# localization-daughter-board.net
KiCad netlist of a schematic drawn in EAGLE
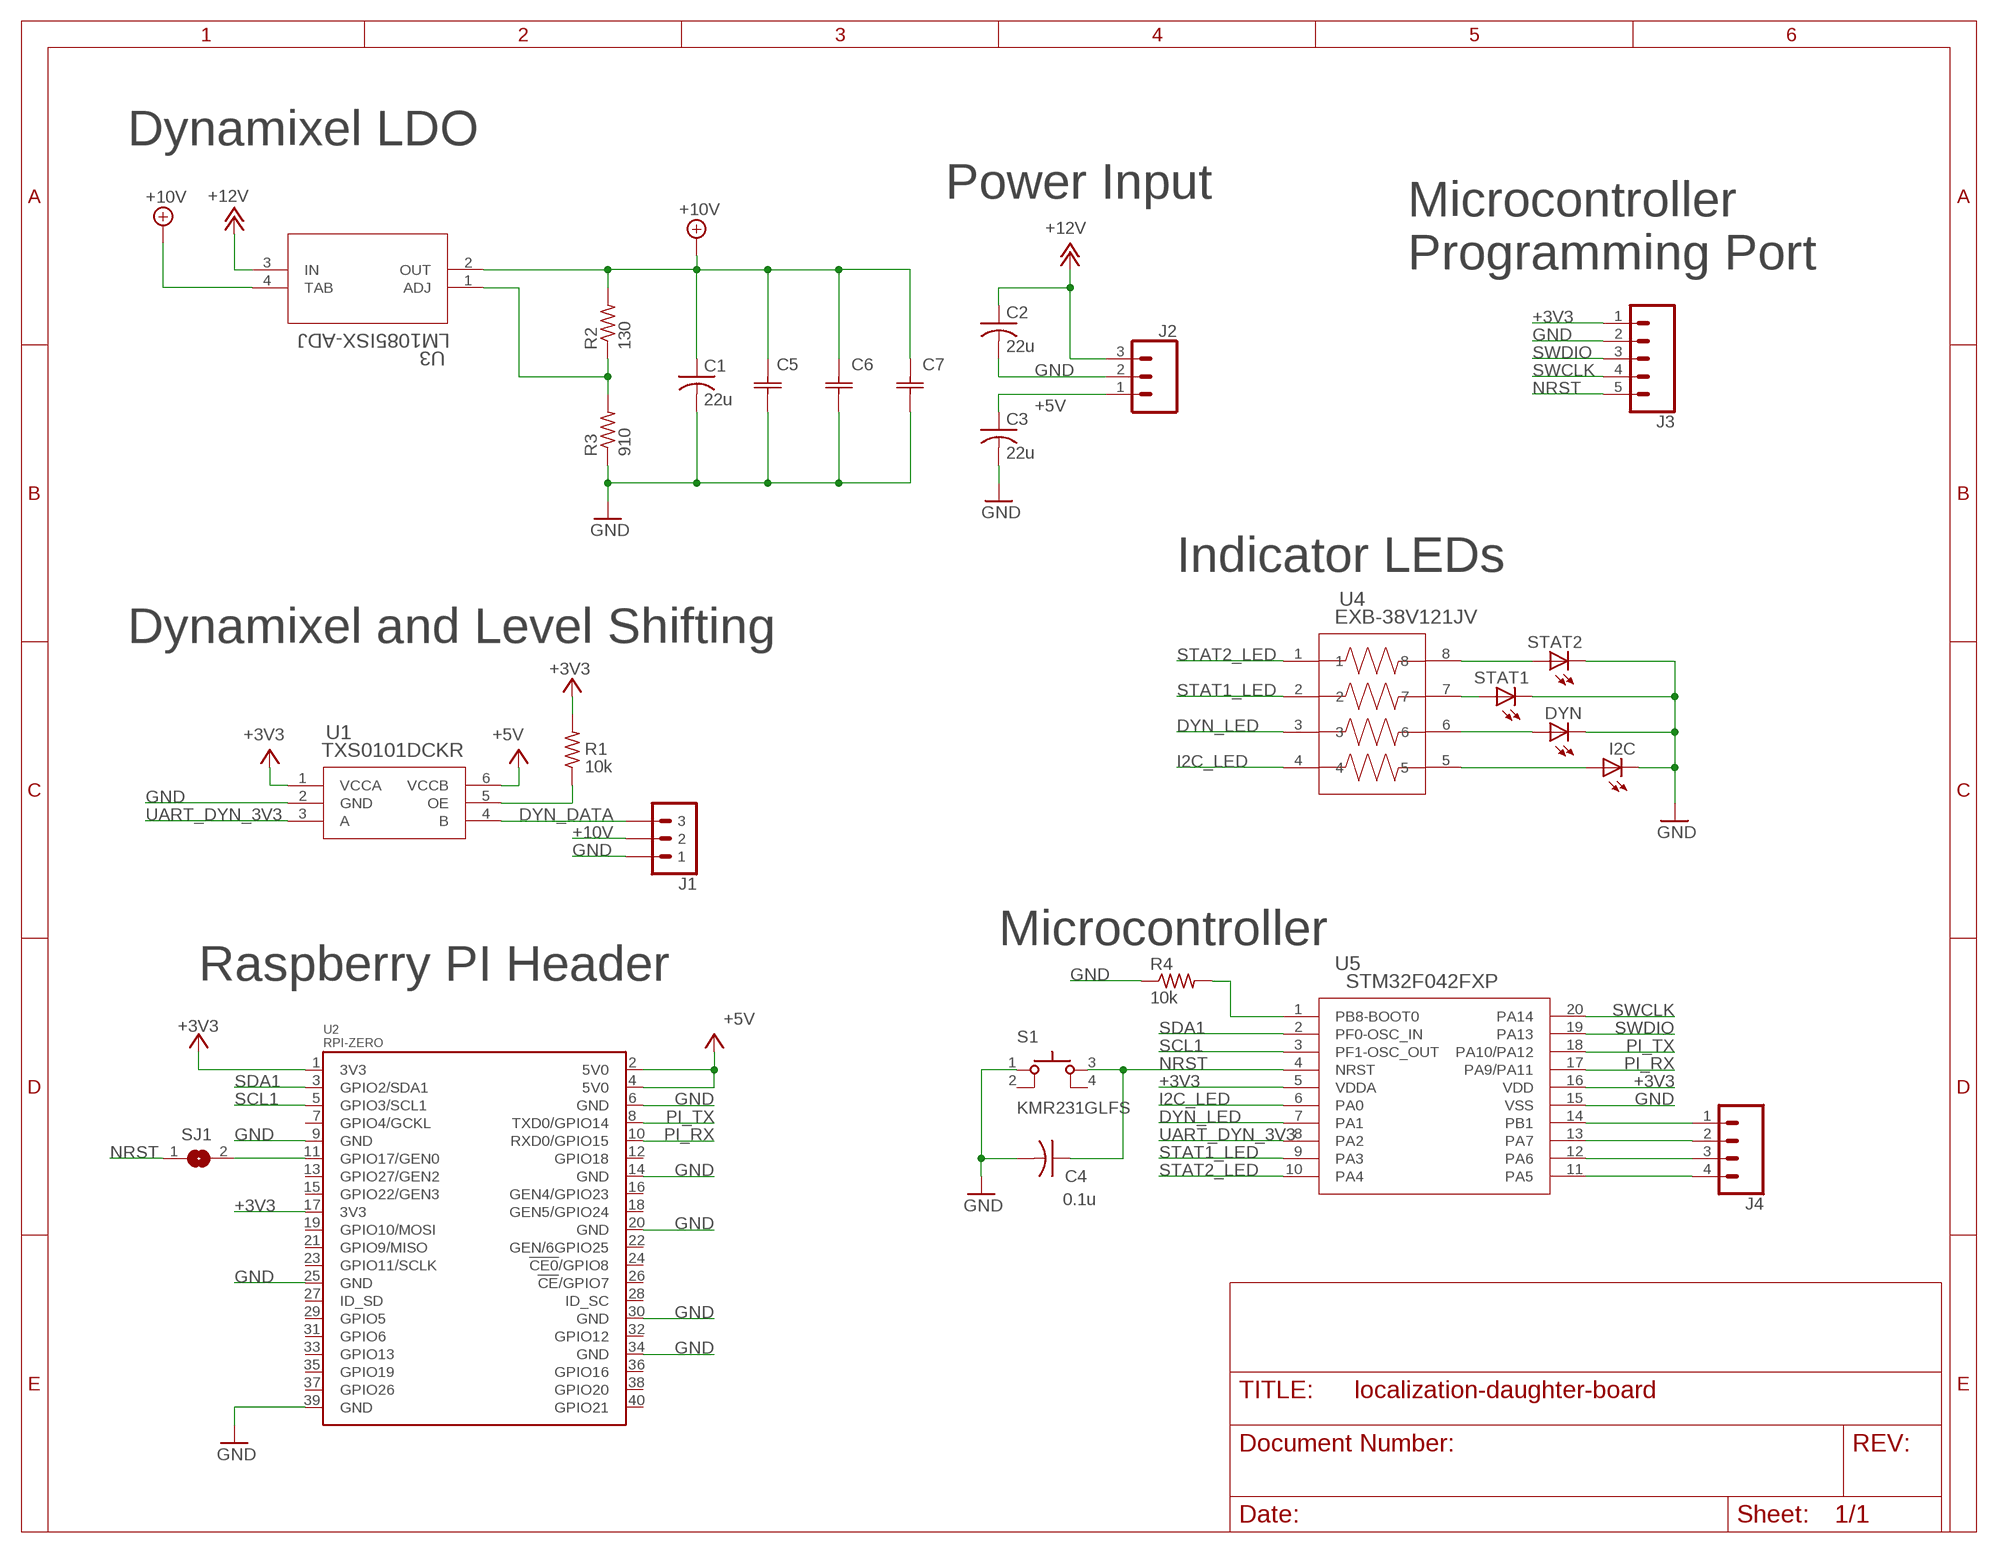
[diagram p0: schematic, sheet 1]

(export (version "E")
  (design (tool "Eeschema 10.0.6"))
  (components
    (comp (ref "C1")
      (value "22u")
      (footprint "eagle-import:C1206")
      (libsource (lib "eagle-import") (part "C-USC1206"))
    )
    (comp (ref "C2")
      (value "22u")
      (footprint "eagle-import:C0805")
      (libsource (lib "eagle-import") (part "C-USC0805"))
    )
    (comp (ref "C3")
      (value "22u")
      (footprint "eagle-import:C0805")
      (libsource (lib "eagle-import") (part "C-USC0805"))
    )
    (comp (ref "C4")
      (value "0.1u")
      (footprint "eagle-import:C0805")
      (libsource (lib "eagle-import") (part "C-USC0805"))
    )
    (comp (ref "C5")
      (value "F931C107MCC")
      (footprint "eagle-import:F93-C")
      (libsource (lib "eagle-import") (part "F931C107MCC"))
    )
    (comp (ref "C6")
      (value "F931C107MCC")
      (footprint "eagle-import:F93-C")
      (libsource (lib "eagle-import") (part "F931C107MCC"))
    )
    (comp (ref "C7")
      (value "F931C107MCC")
      (footprint "eagle-import:F93-C")
      (libsource (lib "eagle-import") (part "F931C107MCC"))
    )
    (comp (ref "DYN")
      (value "LEDSML0603")
      (footprint "eagle-import:SML0603")
      (libsource (lib "eagle-import") (part "LEDSML0603"))
    )
    (comp (ref "I2C")
      (value "LEDSML0603")
      (footprint "eagle-import:SML0603")
      (libsource (lib "eagle-import") (part "LEDSML0603"))
    )
    (comp (ref "J1")
      (value "MOLEX-22-03-5035")
      (footprint "eagle-import:MOLEX-22-05-7035")
      (libsource (lib "eagle-import") (part "MOLEX-22-03-5035"))
    )
    (comp (ref "J2")
      (value "CONN_03JST-PTH")
      (footprint "eagle-import:JST-3-PTH")
      (libsource (lib "eagle-import") (part "CONN_03JST-PTH"))
    )
    (comp (ref "J3")
      (value "CONN_05JST-VERT")
      (footprint "eagle-import:JST-5-PTH-VERT")
      (libsource (lib "eagle-import") (part "CONN_05JST-VERT"))
    )
    (comp (ref "J4")
      (value "CONN_041X04_NO_SILK")
      (footprint "eagle-import:1X04_NO_SILK")
      (libsource (lib "eagle-import") (part "CONN_041X04_NO_SILK"))
    )
    (comp (ref "R1")
      (value "10k")
      (footprint "eagle-import:R0805")
      (libsource (lib "eagle-import") (part "R-US_R0805"))
    )
    (comp (ref "R2")
      (value "130")
      (footprint "eagle-import:R0805")
      (libsource (lib "eagle-import") (part "R-US_R0805"))
    )
    (comp (ref "R3")
      (value "910")
      (footprint "eagle-import:R0805")
      (libsource (lib "eagle-import") (part "R-US_R0805"))
    )
    (comp (ref "R4")
      (value "10k")
      (footprint "eagle-import:R0805")
      (libsource (lib "eagle-import") (part "R-US_R0805"))
    )
    (comp (ref "S1")
      (value "KMR231GLFS")
      (footprint "eagle-import:KMR231GLFS")
      (libsource (lib "eagle-import") (part "KMR231GLFS"))
    )
    (comp (ref "SJ1") (value "SJ") (footprint "eagle-import:SJ") (libsource (lib "eagle-import") (part "SJ")))
    (comp (ref "STAT1")
      (value "LEDSML0603")
      (footprint "eagle-import:SML0603")
      (libsource (lib "eagle-import") (part "LEDSML0603"))
    )
    (comp (ref "STAT2")
      (value "LEDSML0603")
      (footprint "eagle-import:SML0603")
      (libsource (lib "eagle-import") (part "LEDSML0603"))
    )
    (comp (ref "U1")
      (value "TXS0101DCKR")
      (footprint "eagle-import:DCK6")
      (libsource (lib "eagle-import") (part "TXS0101DCKR"))
    )
    (comp (ref "U2")
      (value "RPI-ZERO")
      (footprint "eagle-import:RASPBERRYPI_BASTELSTUBE_V13_RASPI_BOARD_B+_FULL")
      (libsource (lib "eagle-import") (part "RPI-ZERO"))
    )
    (comp (ref "U3")
      (value "LM1085ISX-ADJ")
      (footprint "eagle-import:TS3B")
      (fields (field (name "MANUFACTURER_PART_NUMBER") "lm1085isxadj"))
      (libsource (lib "eagle-import") (part "LM1085ISX-ADJ"))
    )
    (comp (ref "U4")
      (value "EXB-38V121JV")
      (footprint "eagle-import:C_ARRAY_EXB38V")
      (fields (field (name "MANUFACTURER_PART_NUMBER") "EXB38V121JV"))
      (libsource (lib "eagle-import") (part "EXB-38V121JV"))
    )
    (comp (ref "U5")
      (value "STM32F042FXP")
      (footprint "eagle-import:TSSOP20")
      (fields (field (name "MANUFACTURER_PART_NUMBER") "STM32F042FxP"))
      (libsource (lib "eagle-import") (part "STM32F042FXP"))
    )
  )
  (nets
    (net (code "1") (name "+3V3") (class "Default")
      (node (ref "J3") (pin "1") (pinfunction "1_1") (pintype "passive"))
      (node (ref "R1") (pin "2") (pinfunction "2_2") (pintype "passive"))
      (node (ref "U1") (pin "1") (pinfunction "VCCA_1") (pintype "power_in"))
      (node (ref "U2") (pin "1") (pinfunction "3V3_1") (pintype "power_in"))
      (node (ref "U2") (pin "17") (pinfunction "3V3_17") (pintype "power_in"))
      (node (ref "U5") (pin "16") (pinfunction "VDD_16") (pintype "power_in"))
      (node (ref "U5") (pin "5") (pinfunction "VDDA_5") (pintype "power_in"))
    )
    (net (code "2") (name "+5V") (class "Default")
      (node (ref "C3") (pin "1") (pinfunction "1_1") (pintype "passive"))
      (node (ref "J2") (pin "1") (pinfunction "1_1") (pintype "passive"))
      (node (ref "U1") (pin "6") (pinfunction "VCCB_6") (pintype "power_in"))
      (node (ref "U2") (pin "2") (pinfunction "5V0_2") (pintype "power_in"))
      (node (ref "U2") (pin "4") (pinfunction "5V0_4") (pintype "power_in"))
    )
    (net (code "3") (name "+10V") (class "Default")
      (node (ref "C1") (pin "1") (pinfunction "1_1") (pintype "passive"))
      (node (ref "C5") (pin "1") (pinfunction "1_1") (pintype "passive"))
      (node (ref "C6") (pin "1") (pinfunction "1_1") (pintype "passive"))
      (node (ref "C7") (pin "1") (pinfunction "1_1") (pintype "passive"))
      (node (ref "J1") (pin "P$2") (pinfunction "2_P$2") (pintype "bidirectional"))
      (node (ref "R2") (pin "2") (pinfunction "2_2") (pintype "passive"))
      (node (ref "U3") (pin "2") (pinfunction "OUT_2") (pintype "power_in"))
      (node (ref "U3") (pin "4") (pinfunction "TAB_4") (pintype "power_in"))
    )
    (net (code "4") (name "+12V") (class "Default")
      (node (ref "C2") (pin "1") (pinfunction "1_1") (pintype "passive"))
      (node (ref "J2") (pin "3") (pinfunction "3_3") (pintype "passive"))
      (node (ref "U3") (pin "3") (pinfunction "IN_3") (pintype "power_in"))
    )
    (net (code "5") (name "/DYN_DATA") (class "Default")
      (node (ref "J1") (pin "P$3") (pinfunction "3_P$3") (pintype "bidirectional"))
      (node (ref "U1") (pin "4") (pinfunction "B_4") (pintype "bidirectional"))
    )
    (net (code "6") (name "/DYN_LED") (class "Default")
      (node (ref "U4") (pin "3") (pinfunction "3_3") (pintype "passive"))
      (node (ref "U5") (pin "7") (pinfunction "PA1_7") (pintype "bidirectional"))
    )
    (net (code "7") (name "/I2C_LED") (class "Default")
      (node (ref "U4") (pin "4") (pinfunction "4_4") (pintype "passive"))
      (node (ref "U5") (pin "6") (pinfunction "PA0_6") (pintype "bidirectional"))
    )
    (net (code "8") (name "/NRST") (class "Default")
      (node (ref "C4") (pin "1") (pinfunction "1_1") (pintype "passive"))
      (node (ref "J3") (pin "5") (pinfunction "5_5") (pintype "passive"))
      (node (ref "S1") (pin "3") (pinfunction "3_3") (pintype "bidirectional"))
      (node (ref "SJ1") (pin "1") (pinfunction "1_1") (pintype "passive"))
      (node (ref "U5") (pin "4") (pinfunction "NRST_4") (pintype "bidirectional"))
    )
    (net (code "9") (name "/PI_RX") (class "Default")
      (node (ref "U2") (pin "10") (pinfunction "RXD0/GPIO15_10") (pintype "bidirectional"))
      (node (ref "U5") (pin "17") (pinfunction "PA9/PA11_17") (pintype "bidirectional"))
    )
    (net (code "10") (name "/PI_TX") (class "Default")
      (node (ref "U2") (pin "8") (pinfunction "TXD0/GPIO14_8") (pintype "bidirectional"))
      (node (ref "U5") (pin "18") (pinfunction "PA10/PA12_18") (pintype "bidirectional"))
    )
    (net (code "11") (name "/SCL1") (class "Default")
      (node (ref "U2") (pin "5") (pinfunction "GPIO3/SCL1_5") (pintype "bidirectional"))
      (node (ref "U5") (pin "3") (pinfunction "PF1-OSC_OUT_3") (pintype "bidirectional"))
    )
    (net (code "12") (name "/SDA1") (class "Default")
      (node (ref "U2") (pin "3") (pinfunction "GPIO2/SDA1_3") (pintype "bidirectional"))
      (node (ref "U5") (pin "2") (pinfunction "PF0-OSC_IN_2") (pintype "bidirectional"))
    )
    (net (code "13") (name "/STAT1_LED") (class "Default")
      (node (ref "U4") (pin "2") (pinfunction "2_2") (pintype "passive"))
      (node (ref "U5") (pin "9") (pinfunction "PA3_9") (pintype "bidirectional"))
    )
    (net (code "14") (name "/STAT2_LED") (class "Default")
      (node (ref "U4") (pin "1") (pinfunction "1_1") (pintype "passive"))
      (node (ref "U5") (pin "10") (pinfunction "PA4_10") (pintype "bidirectional"))
    )
    (net (code "15") (name "/SWCLK") (class "Default")
      (node (ref "J3") (pin "4") (pinfunction "4_4") (pintype "passive"))
      (node (ref "U5") (pin "20") (pinfunction "PA14_20") (pintype "bidirectional"))
    )
    (net (code "16") (name "/SWDIO") (class "Default")
      (node (ref "J3") (pin "3") (pinfunction "3_3") (pintype "passive"))
      (node (ref "U5") (pin "19") (pinfunction "PA13_19") (pintype "bidirectional"))
    )
    (net (code "17") (name "/UART_DYN_3V3") (class "Default")
      (node (ref "U1") (pin "3") (pinfunction "A_3") (pintype "bidirectional"))
      (node (ref "U5") (pin "8") (pinfunction "PA2_8") (pintype "bidirectional"))
    )
    (net (code "18") (name "GND") (class "Default")
      (node (ref "C1") (pin "2") (pinfunction "2_2") (pintype "passive"))
      (node (ref "C2") (pin "2") (pinfunction "2_2") (pintype "passive"))
      (node (ref "C3") (pin "2") (pinfunction "2_2") (pintype "passive"))
      (node (ref "C4") (pin "2") (pinfunction "2_2") (pintype "passive"))
      (node (ref "C5") (pin "2") (pinfunction "2_2") (pintype "passive"))
      (node (ref "C6") (pin "2") (pinfunction "2_2") (pintype "passive"))
      (node (ref "C7") (pin "2") (pinfunction "2_2") (pintype "passive"))
      (node (ref "DYN") (pin "C") (pinfunction "C_C") (pintype "passive"))
      (node (ref "I2C") (pin "C") (pinfunction "C_C") (pintype "passive"))
      (node (ref "J1") (pin "P$1") (pinfunction "1_P$1") (pintype "bidirectional"))
      (node (ref "J2") (pin "2") (pinfunction "2_2") (pintype "passive"))
      (node (ref "J3") (pin "2") (pinfunction "2_2") (pintype "passive"))
      (node (ref "R3") (pin "1") (pinfunction "1_1") (pintype "passive"))
      (node (ref "R4") (pin "1") (pinfunction "1_1") (pintype "passive"))
      (node (ref "S1") (pin "1") (pinfunction "1_1") (pintype "bidirectional"))
      (node (ref "STAT1") (pin "C") (pinfunction "C_C") (pintype "passive"))
      (node (ref "STAT2") (pin "C") (pinfunction "C_C") (pintype "passive"))
      (node (ref "U1") (pin "2") (pinfunction "GND_2") (pintype "power_in"))
      (node (ref "U2") (pin "14") (pinfunction "GND_14") (pintype "power_in"))
      (node (ref "U2") (pin "20") (pinfunction "GND_20") (pintype "power_in"))
      (node (ref "U2") (pin "25") (pinfunction "GND_25") (pintype "power_in"))
      (node (ref "U2") (pin "30") (pinfunction "GND_30") (pintype "power_in"))
      (node (ref "U2") (pin "34") (pinfunction "GND_34") (pintype "power_in"))
      (node (ref "U2") (pin "39") (pinfunction "GND_39") (pintype "power_in"))
      (node (ref "U2") (pin "6") (pinfunction "GND_6") (pintype "power_in"))
      (node (ref "U2") (pin "9") (pinfunction "GND_9") (pintype "power_in"))
      (node (ref "U5") (pin "15") (pinfunction "VSS_15") (pintype "power_in"))
    )
    (net (code "19") (name "Net-(DYN-PadA)") (class "Default")
      (node (ref "DYN") (pin "A") (pinfunction "A_A") (pintype "passive"))
      (node (ref "U4") (pin "6") (pinfunction "6_6") (pintype "passive"))
    )
    (net (code "20") (name "Net-(I2C-PadA)") (class "Default")
      (node (ref "I2C") (pin "A") (pinfunction "A_A") (pintype "passive"))
      (node (ref "U4") (pin "5") (pinfunction "5_5") (pintype "passive"))
    )
    (net (code "21") (name "Net-(STAT1-PadA)") (class "Default")
      (node (ref "STAT1") (pin "A") (pinfunction "A_A") (pintype "passive"))
      (node (ref "U4") (pin "7") (pinfunction "7_7") (pintype "passive"))
    )
    (net (code "22") (name "Net-(STAT2-PadA)") (class "Default")
      (node (ref "STAT2") (pin "A") (pinfunction "A_A") (pintype "passive"))
      (node (ref "U4") (pin "8") (pinfunction "8_8") (pintype "passive"))
    )
    (net (code "23") (name "Net-(U1-OE)") (class "Default")
      (node (ref "R1") (pin "1") (pinfunction "1_1") (pintype "passive"))
      (node (ref "U1") (pin "5") (pinfunction "OE_5") (pintype "output"))
    )
    (net (code "24") (name "Net-(U2-GPIO17{slash}GEN0)") (class "Default")
      (node (ref "SJ1") (pin "2") (pinfunction "2_2") (pintype "passive"))
      (node (ref "U2") (pin "11") (pinfunction "GPIO17/GEN0_11") (pintype "bidirectional"))
    )
    (net (code "25") (name "Net-(U3-ADJ)") (class "Default")
      (node (ref "R2") (pin "1") (pinfunction "1_1") (pintype "passive"))
      (node (ref "R3") (pin "2") (pinfunction "2_2") (pintype "passive"))
      (node (ref "U3") (pin "1") (pinfunction "ADJ_1") (pintype "input"))
    )
    (net (code "26") (name "Net-(U5-PA5)") (class "Default")
      (node (ref "J4") (pin "4") (pinfunction "4_4") (pintype "passive"))
      (node (ref "U5") (pin "11") (pinfunction "PA5_11") (pintype "bidirectional"))
    )
    (net (code "27") (name "Net-(U5-PA6)") (class "Default")
      (node (ref "J4") (pin "3") (pinfunction "3_3") (pintype "passive"))
      (node (ref "U5") (pin "12") (pinfunction "PA6_12") (pintype "bidirectional"))
    )
    (net (code "28") (name "Net-(U5-PA7)") (class "Default")
      (node (ref "J4") (pin "2") (pinfunction "2_2") (pintype "passive"))
      (node (ref "U5") (pin "13") (pinfunction "PA7_13") (pintype "bidirectional"))
    )
    (net (code "29") (name "Net-(U5-PB1)") (class "Default")
      (node (ref "J4") (pin "1") (pinfunction "1_1") (pintype "passive"))
      (node (ref "U5") (pin "14") (pinfunction "PB1_14") (pintype "bidirectional"))
    )
    (net (code "30") (name "Net-(U5-PB8-BOOT0)") (class "Default")
      (node (ref "R4") (pin "2") (pinfunction "2_2") (pintype "passive"))
      (node (ref "U5") (pin "1") (pinfunction "PB8-BOOT0_1") (pintype "bidirectional"))
    )
    (net (code "31") (name "unconnected-(S1-Pad2)") (class "Default")
      (node (ref "S1") (pin "2") (pinfunction "2_2") (pintype "bidirectional"))
    )
    (net (code "32") (name "unconnected-(S1-Pad4)") (class "Default")
      (node (ref "S1") (pin "4") (pinfunction "4_4") (pintype "bidirectional"))
    )
    (net (code "33") (name "unconnected-(U2-GEN4{slash}GPIO23-Pad16)") (class "Default")
      (node (ref "U2") (pin "16") (pinfunction "GEN4/GPIO23_16") (pintype "bidirectional"))
    )
    (net (code "34") (name "unconnected-(U2-GEN5{slash}GPIO24-Pad18)") (class "Default")
      (node (ref "U2") (pin "18") (pinfunction "GEN5/GPIO24_18") (pintype "bidirectional"))
    )
    (net (code "35") (name "unconnected-(U2-GEN{slash}6GPIO25-Pad22)") (class "Default")
      (node (ref "U2") (pin "22") (pinfunction "GEN/6GPIO25_22") (pintype "bidirectional"))
    )
    (net (code "36") (name "unconnected-(U2-GPIO4{slash}GCKL-Pad7)") (class "Default")
      (node (ref "U2") (pin "7") (pinfunction "GPIO4/GCKL_7") (pintype "bidirectional"))
    )
    (net (code "37") (name "unconnected-(U2-GPIO5-Pad29)") (class "Default")
      (node (ref "U2") (pin "29") (pinfunction "GPIO5_29") (pintype "bidirectional"))
    )
    (net (code "38") (name "unconnected-(U2-GPIO6-Pad31)") (class "Default")
      (node (ref "U2") (pin "31") (pinfunction "GPIO6_31") (pintype "bidirectional"))
    )
    (net (code "39") (name "unconnected-(U2-GPIO9{slash}MISO-Pad21)") (class "Default")
      (node (ref "U2") (pin "21") (pinfunction "GPIO9/MISO_21") (pintype "bidirectional"))
    )
    (net (code "40") (name "unconnected-(U2-GPIO10{slash}MOSI-Pad19)") (class "Default")
      (node (ref "U2") (pin "19") (pinfunction "GPIO10/MOSI_19") (pintype "bidirectional"))
    )
    (net (code "41") (name "unconnected-(U2-GPIO11{slash}SCLK-Pad23)") (class "Default")
      (node (ref "U2") (pin "23") (pinfunction "GPIO11/SCLK_23") (pintype "bidirectional"))
    )
    (net (code "42") (name "unconnected-(U2-GPIO12-Pad32)") (class "Default")
      (node (ref "U2") (pin "32") (pinfunction "GPIO12_32") (pintype "bidirectional"))
    )
    (net (code "43") (name "unconnected-(U2-GPIO13-Pad33)") (class "Default")
      (node (ref "U2") (pin "33") (pinfunction "GPIO13_33") (pintype "bidirectional"))
    )
    (net (code "44") (name "unconnected-(U2-GPIO16-Pad36)") (class "Default")
      (node (ref "U2") (pin "36") (pinfunction "GPIO16_36") (pintype "bidirectional"))
    )
    (net (code "45") (name "unconnected-(U2-GPIO18-Pad12)") (class "Default")
      (node (ref "U2") (pin "12") (pinfunction "GPIO18_12") (pintype "bidirectional"))
    )
    (net (code "46") (name "unconnected-(U2-GPIO19-Pad35)") (class "Default")
      (node (ref "U2") (pin "35") (pinfunction "GPIO19_35") (pintype "bidirectional"))
    )
    (net (code "47") (name "unconnected-(U2-GPIO20-Pad38)") (class "Default")
      (node (ref "U2") (pin "38") (pinfunction "GPIO20_38") (pintype "bidirectional"))
    )
    (net (code "48") (name "unconnected-(U2-GPIO21-Pad40)") (class "Default")
      (node (ref "U2") (pin "40") (pinfunction "GPIO21_40") (pintype "bidirectional"))
    )
    (net (code "49") (name "unconnected-(U2-GPIO22{slash}GEN3-Pad15)") (class "Default")
      (node (ref "U2") (pin "15") (pinfunction "GPIO22/GEN3_15") (pintype "bidirectional"))
    )
    (net (code "50") (name "unconnected-(U2-GPIO26-Pad37)") (class "Default")
      (node (ref "U2") (pin "37") (pinfunction "GPIO26_37") (pintype "bidirectional"))
    )
    (net (code "51") (name "unconnected-(U2-GPIO27{slash}GEN2-Pad13)") (class "Default")
      (node (ref "U2") (pin "13") (pinfunction "GPIO27/GEN2_13") (pintype "bidirectional"))
    )
    (net (code "52") (name "unconnected-(U2-ID_SC-Pad28)") (class "Default")
      (node (ref "U2") (pin "28") (pinfunction "ID_SC_28") (pintype "bidirectional"))
    )
    (net (code "53") (name "unconnected-(U2-ID_SD-Pad27)") (class "Default")
      (node (ref "U2") (pin "27") (pinfunction "ID_SD_27") (pintype "bidirectional"))
    )
    (net (code "54") (name "unconnected-(U2-~{CE0}{slash}GPIO8-Pad24)") (class "Default")
      (node (ref "U2") (pin "24") (pinfunction "~{CE0}/GPIO8_24") (pintype "bidirectional"))
    )
    (net (code "55") (name "unconnected-(U2-~{CE}{slash}GPIO7-Pad26)") (class "Default")
      (node (ref "U2") (pin "26") (pinfunction "~{CE}/GPIO7_26") (pintype "bidirectional"))
    )
  )
)
